# 11_Audio_Interface.net
KiCad netlist of a schematic drawn in Altium Designer
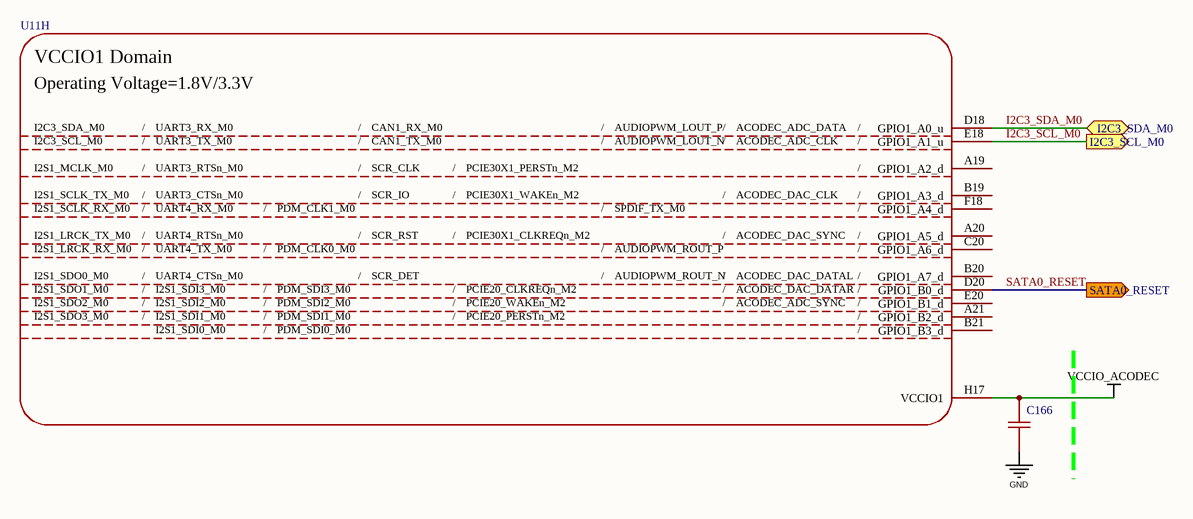
[diagram p0: 11_Audio Interface.schdoc]

(export (version "E")
  (design (tool "Eeschema 10.0.6"))
  (components
    (comp (ref "C166")
      (value "100nF")
      (footprint "C0201")
      (description "容值:100nF;精度:±10%;额定电压:16V;材质(温度系数):X5R;")
      (fields
        (field (name "MANUFACTURER") "SAMSUNG(三星)")
        (field (name "MANUFACTURER PART") "CL03A104KO3NNNC")
      )
      (libsource (lib "altium-import") (part "root_0_CL03A104KO3NNNC_"))
    )
    (comp (ref "U11")
      (value "SOC_RK3568")
      (footprint "RK3568")
      (fields (field (name "MANUFACTURER") "Rockchip (瑞芯微)") (field (name "CREATED BY") "JJJ"))
      (libsource (lib "altium-import") (part "root_0_SOC_RK3568_"))
    )
  )
  (nets
    (net (code "1") (name "/I2C3_SCL_M0") (class "Default")
      (node (ref "U11") (pin "E18") (pinfunction "GPIO1_A1_u_E18") (pintype "passive"))
    )
    (net (code "2") (name "/I2C3_SDA_M0") (class "Default")
      (node (ref "U11") (pin "D18") (pinfunction "GPIO1_A0_u_D18") (pintype "passive"))
    )
    (net (code "3") (name "/SATA0_RESET") (class "Default")
      (node (ref "U11") (pin "D20") (pinfunction "GPIO1_B0_d_D20") (pintype "passive"))
    )
    (net (code "4") (name "GND") (class "Default")
      (node (ref "C166") (pin "1") (pinfunction "1_1") (pintype "passive"))
    )
    (net (code "5") (name "VCCIO_ACODEC") (class "Default")
      (node (ref "C166") (pin "2") (pinfunction "2_2") (pintype "passive"))
      (node (ref "U11") (pin "H17") (pinfunction "VCCIO1_H17") (pintype "passive"))
    )
    (net (code "6") (name "unconnected-(U11H-GPIO1_A2_d-PadA19)") (class "Default")
      (node (ref "U11") (pin "A19") (pinfunction "GPIO1_A2_d_A19") (pintype "passive"))
    )
    (net (code "7") (name "unconnected-(U11H-GPIO1_A3_d-PadB19)") (class "Default")
      (node (ref "U11") (pin "B19") (pinfunction "GPIO1_A3_d_B19") (pintype "passive"))
    )
    (net (code "8") (name "unconnected-(U11H-GPIO1_A4_d-PadF18)") (class "Default")
      (node (ref "U11") (pin "F18") (pinfunction "GPIO1_A4_d_F18") (pintype "passive"))
    )
    (net (code "9") (name "unconnected-(U11H-GPIO1_A5_d-PadA20)") (class "Default")
      (node (ref "U11") (pin "A20") (pinfunction "GPIO1_A5_d_A20") (pintype "passive"))
    )
    (net (code "10") (name "unconnected-(U11H-GPIO1_A6_d-PadC20)") (class "Default")
      (node (ref "U11") (pin "C20") (pinfunction "GPIO1_A6_d_C20") (pintype "passive"))
    )
    (net (code "11") (name "unconnected-(U11H-GPIO1_A7_d-PadB20)") (class "Default")
      (node (ref "U11") (pin "B20") (pinfunction "GPIO1_A7_d_B20") (pintype "passive"))
    )
    (net (code "12") (name "unconnected-(U11H-GPIO1_B1_d-PadE20)") (class "Default")
      (node (ref "U11") (pin "E20") (pinfunction "GPIO1_B1_d_E20") (pintype "passive"))
    )
    (net (code "13") (name "unconnected-(U11H-GPIO1_B2_d-PadA21)") (class "Default")
      (node (ref "U11") (pin "A21") (pinfunction "GPIO1_B2_d_A21") (pintype "passive"))
    )
    (net (code "14") (name "unconnected-(U11H-GPIO1_B3_d-PadB21)") (class "Default")
      (node (ref "U11") (pin "B21") (pinfunction "GPIO1_B3_d_B21") (pintype "passive"))
    )
  )
)
